# Enclosure_100x68_BHCP.net
KiCad netlist of a schematic drawn in EAGLE
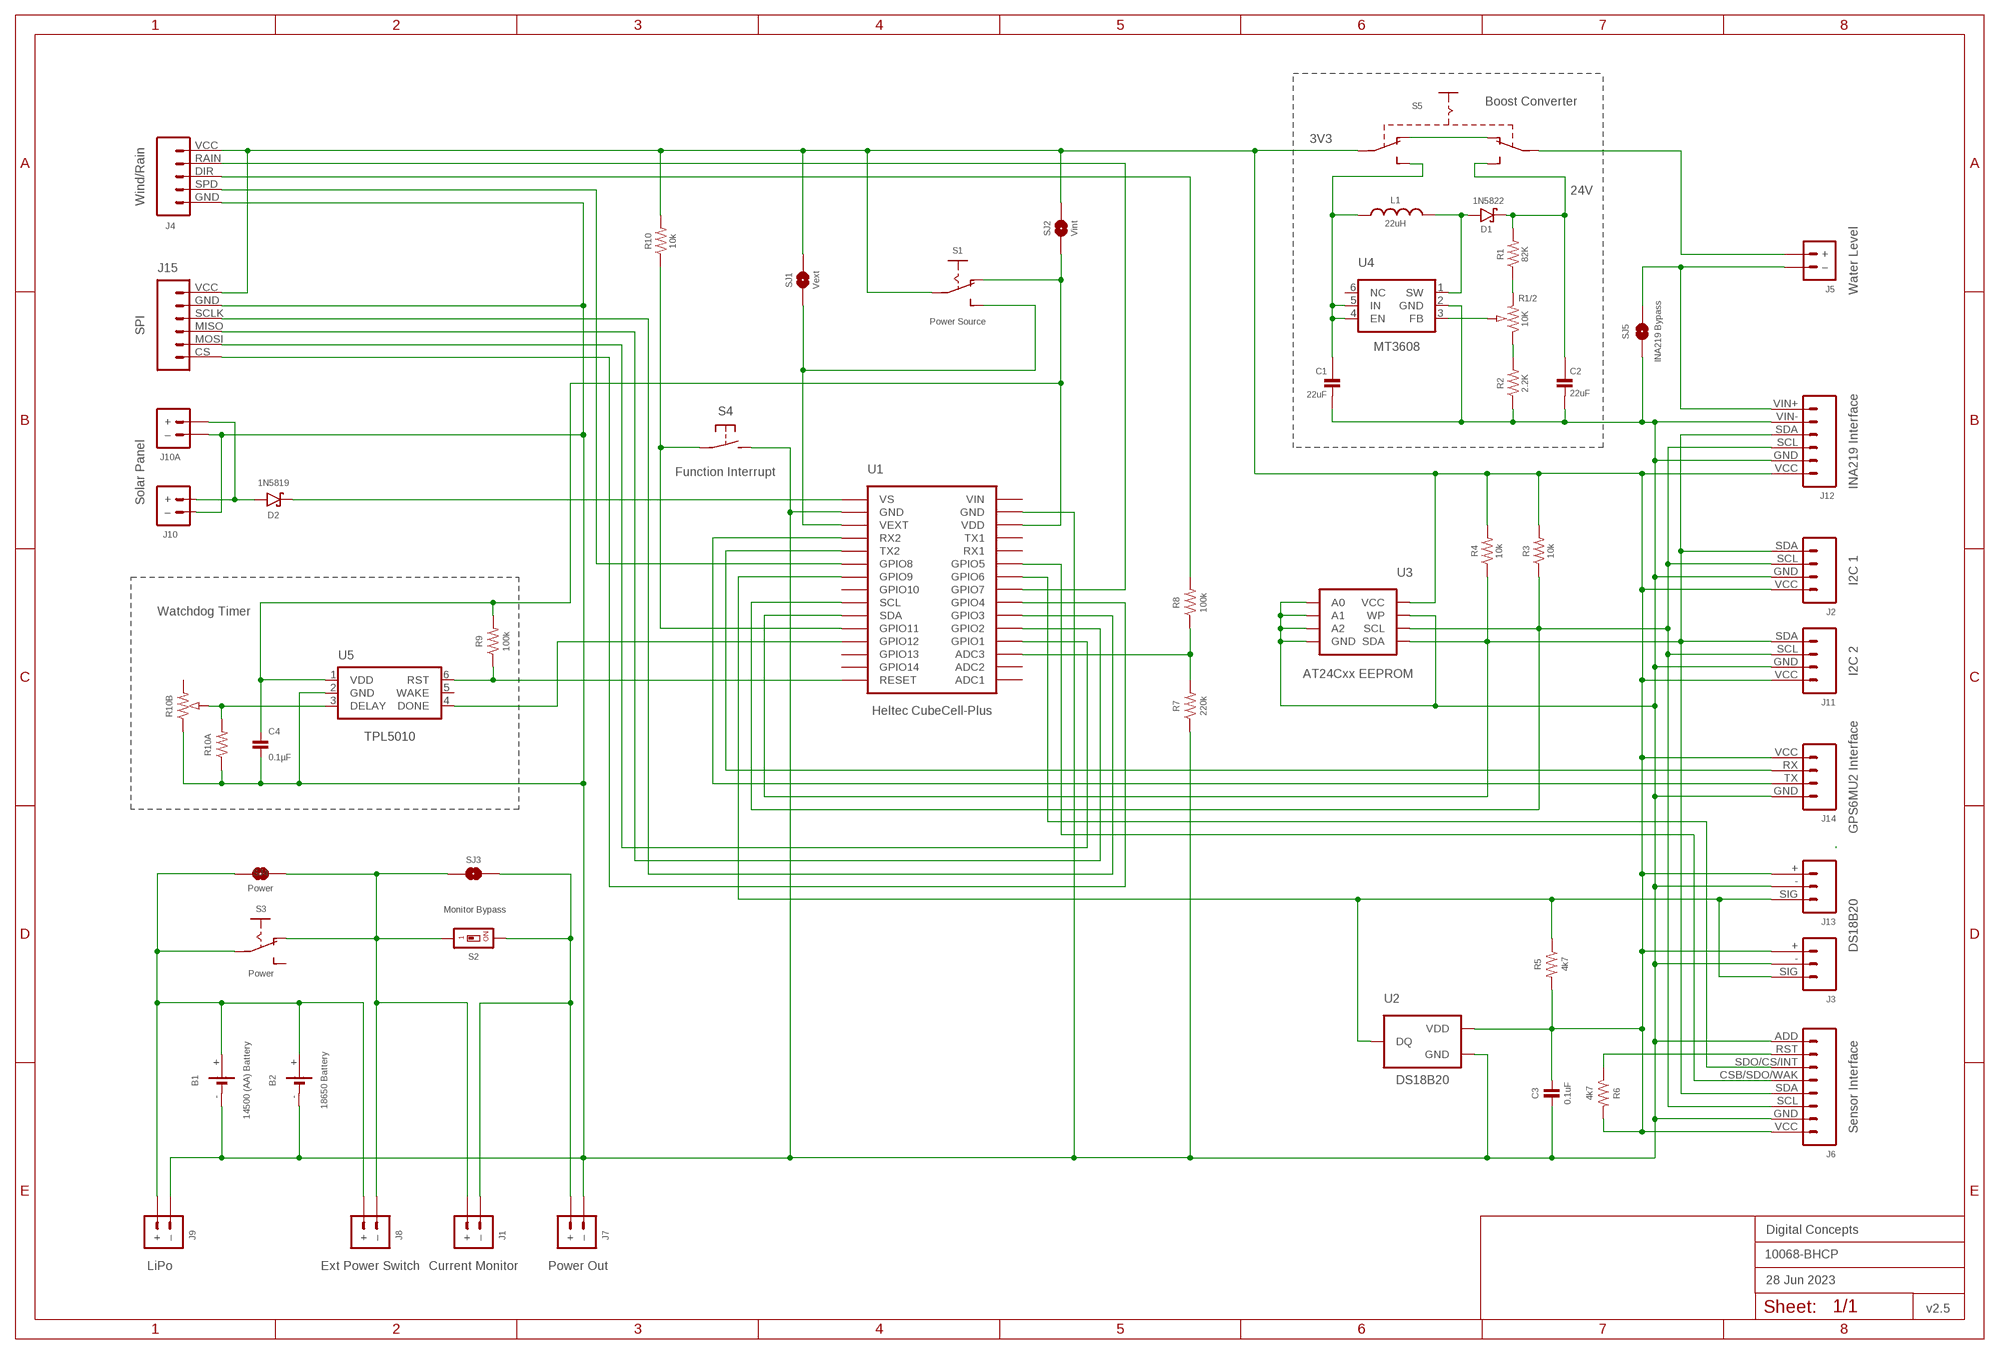
[diagram p0: schematic, sheet 1]

(export (version "E")
  (design (tool "Eeschema 10.0.6"))
  (components
    (comp (ref "B1")
      (value "14500 (AA) Battery")
      (footprint "eagle-import:BATTERY-14500")
      (libsource (lib "eagle-import") (part "BATTERY-HOLDER-14500(AA)"))
    )
    (comp (ref "B2")
      (value "18650 Battery")
      (footprint "eagle-import:BATTERY-18650")
      (libsource (lib "eagle-import") (part "BATTERY-HOLDER-18650"))
    )
    (comp (ref "C1")
      (value "22uF")
      (footprint "eagle-import:C1206")
      (libsource (lib "eagle-import") (part "CAPACITOR-1206"))
    )
    (comp (ref "C2")
      (value "22uF")
      (footprint "eagle-import:C1206")
      (libsource (lib "eagle-import") (part "CAPACITOR-1206"))
    )
    (comp (ref "C3")
      (value "0.1uF")
      (footprint "eagle-import:C0805")
      (libsource (lib "eagle-import") (part "CAPACITOR-0805"))
    )
    (comp (ref "C4")
      (value "0.1µF")
      (footprint "eagle-import:C0805")
      (libsource (lib "eagle-import") (part "CAPACITOR-0805"))
    )
    (comp (ref "D1")
      (value "1N5822")
      (footprint "eagle-import:DIODE_SMB")
      (libsource (lib "eagle-import") (part "DIODE-SCHOTTKY-1N5822"))
    )
    (comp (ref "D2")
      (value "1N5819")
      (footprint "eagle-import:SOD-123")
      (libsource (lib "eagle-import") (part "1N5819-SOD-123"))
    )
    (comp (ref "J1")
      (value "Current Monitor")
      (footprint "eagle-import:JST-PH2.0-2-HORIZONTAL")
      (libsource (lib "eagle-import") (part "JST-PH2.0-2-HORIZONTALJST-PTH-2"))
    )
    (comp (ref "J2")
      (value "I2C 1")
      (footprint "eagle-import:JST-PH2.0-4-VERTICAL-I2C")
      (libsource (lib "eagle-import") (part "JST-PH2.0-4-VERTICAL-I2C"))
    )
    (comp (ref "J3")
      (value "DS18B20")
      (footprint "eagle-import:JST-PH2.0-3-VERTICAL-SIG")
      (libsource (lib "eagle-import") (part "JST-PH2.0-3-VERTICAL-DS18B20"))
    )
    (comp (ref "J4")
      (value "Wind/Rain")
      (footprint "eagle-import:JST-PH2.0-5-DUAL-WEATHER")
      (libsource (lib "eagle-import") (part "JST-PH2.0-5-DUAL-WEATHER"))
    )
    (comp (ref "J5")
      (value "Water Level")
      (footprint "eagle-import:JST-PH2.0-2-DUAL-POWER")
      (libsource (lib "eagle-import") (part "JST-PH2.0-2-DUAL-POWERJST-PTH-2"))
    )
    (comp (ref "J6")
      (value "Sensor Interface")
      (footprint "eagle-import:CONN_08-SENSOR")
      (libsource (lib "eagle-import") (part "HEADER-1X8-SENSOR"))
    )
    (comp (ref "J7")
      (value "Power Out")
      (footprint "eagle-import:JST-GH1.25-2-HORIZONTAL")
      (libsource (lib "eagle-import") (part "JST-GH1.25-2-HORIZONTAL-POWER"))
    )
    (comp (ref "J8")
      (value "Ext Power Switch")
      (footprint "eagle-import:JST-PH2.0-2-DUAL-POWER")
      (libsource (lib "eagle-import") (part "JST-PH2.0-2-DUAL-POWERJST-PTH-2"))
    )
    (comp (ref "J9")
      (value "LiPo")
      (footprint "eagle-import:JST-PH2.0-2-HORIZONTAL-POWER")
      (libsource (lib "eagle-import") (part "JST-PH2.0-2-HORIZONTAL-POWERJST-PTH-2"))
    )
    (comp (ref "J10")
      (value "Solar Panel")
      (footprint "eagle-import:JST-PH2.0-2-VERTICAL=POWER")
      (libsource (lib "eagle-import") (part "JST-PH2.0-2-VERTICAL"))
    )
    (comp (ref "J10A")
      (value "JST-PH2.0-2-HORIZONTAL-POWERJST-PTH-2")
      (footprint "eagle-import:JST-PH2.0-2-HORIZONTAL-POWER")
      (libsource (lib "eagle-import") (part "JST-PH2.0-2-HORIZONTAL-POWERJST-PTH-2"))
    )
    (comp (ref "J11")
      (value "I2C 2")
      (footprint "eagle-import:JST-PH2.0-4-HORIZONTAL")
      (libsource (lib "eagle-import") (part "JST-PH2.0-I2C-MALE-HORIZONTAL"))
    )
    (comp (ref "J12")
      (value "INA219 Interface")
      (footprint "eagle-import:CONN_06-INA219")
      (libsource (lib "eagle-import") (part "INA219-I2C-MODULE"))
    )
    (comp (ref "J13")
      (value "JST-PH2.0-3-HORIZONTAL-DS18B20")
      (footprint "eagle-import:JST-PH2.0-DS18B20-HORIZONTAL")
      (libsource (lib "eagle-import") (part "JST-PH2.0-3-HORIZONTAL-DS18B20"))
    )
    (comp (ref "J14")
      (value "GPS6MU2 Interface")
      (footprint "eagle-import:CONN_04-GPS")
      (libsource (lib "eagle-import") (part "HEADER-1X4-GPS"))
    )
    (comp (ref "J15")
      (value "SPI")
      (footprint "eagle-import:JST-PH2.0-6-HORIZONTAL-SPI")
      (libsource (lib "eagle-import") (part "JST-PH2.0-6-HORIZONTAL-SPI"))
    )
    (comp (ref "L1")
      (value "22uH")
      (footprint "eagle-import:CDRH104R+6D28")
      (libsource (lib "eagle-import") (part "INDUCTOR-CDRH104R/6D28L5038P"))
    )
    (comp (ref "R1")
      (value "82K")
      (footprint "eagle-import:R0805")
      (libsource (lib "eagle-import") (part "RESISTORR0805"))
    )
    (comp (ref "R1/2")
      (value "10K")
      (footprint "eagle-import:RTRIM64P")
      (libsource (lib "eagle-import") (part "RESISTOR-TRIMM-BAOTER-H-US"))
    )
    (comp (ref "R2")
      (value "2.2K")
      (footprint "eagle-import:R0805")
      (libsource (lib "eagle-import") (part "RESISTORR0805"))
    )
    (comp (ref "R3")
      (value "10k")
      (footprint "eagle-import:R0805")
      (libsource (lib "eagle-import") (part "RESISTORR0805"))
    )
    (comp (ref "R4")
      (value "10k")
      (footprint "eagle-import:R0805")
      (libsource (lib "eagle-import") (part "RESISTORR0805"))
    )
    (comp (ref "R5")
      (value "4k7")
      (footprint "eagle-import:R0805")
      (libsource (lib "eagle-import") (part "RESISTORR0805"))
    )
    (comp (ref "R6")
      (value "4k7")
      (footprint "eagle-import:R0805")
      (libsource (lib "eagle-import") (part "RESISTORR0805"))
    )
    (comp (ref "R7")
      (value "220k")
      (footprint "eagle-import:R0805")
      (libsource (lib "eagle-import") (part "RESISTORR0805"))
    )
    (comp (ref "R8")
      (value "100k")
      (footprint "eagle-import:R0805")
      (libsource (lib "eagle-import") (part "RESISTORR0805"))
    )
    (comp (ref "R9")
      (value "100k")
      (footprint "eagle-import:R0805")
      (libsource (lib "eagle-import") (part "RESISTORR0805"))
    )
    (comp (ref "R10")
      (value "10k")
      (footprint "eagle-import:R0805")
      (libsource (lib "eagle-import") (part "RESISTORR0805"))
    )
    (comp (ref "R10A")
      (value "RESISTORR0805")
      (footprint "eagle-import:R0805")
      (libsource (lib "eagle-import") (part "RESISTORR0805"))
    )
    (comp (ref "R10B")
      (value "RESISTOR-TRIMM-33-US")
      (footprint "eagle-import:RTRIM3_3")
      (libsource (lib "eagle-import") (part "RESISTOR-TRIMM-33-US"))
    )
    (comp (ref "S1")
      (value "Power Source")
      (footprint "eagle-import:SWITCH-SPDT-SMT")
      (libsource (lib "eagle-import") (part "SWITCH-SLIDE-SPDT-SMT"))
    )
    (comp (ref "S2")
      (value "Monitor Bypass")
      (footprint "eagle-import:SMD-001")
      (libsource (lib "eagle-import") (part "SWITCH-DIP-SWS001"))
    )
    (comp (ref "S3")
      (value "Power")
      (footprint "eagle-import:SWITCH-SPDT-PTH")
      (libsource (lib "eagle-import") (part "SWITCH-SLIDE-SPDT-PTH"))
    )
    (comp (ref "S4")
      (value "Function Interrupt")
      (footprint "eagle-import:SWITCH-2-PAD")
      (libsource (lib "eagle-import") (part "SWITCH-MOMENTARY-2-PIN"))
    )
    (comp (ref "S5")
      (value "SWITCH-SLIDE-DPDT-PTH-S")
      (footprint "eagle-import:SWITCH-DPDT-PTH")
      (libsource (lib "eagle-import") (part "SWITCH-SLIDE-DPDT-PTH-S"))
    )
    (comp (ref "SJ1")
      (value "Vext")
      (footprint "eagle-import:SJ")
      (libsource (lib "eagle-import") (part "SJ"))
    )
    (comp (ref "SJ2")
      (value "Vint")
      (footprint "eagle-import:SJ-VIA-12")
      (libsource (lib "eagle-import") (part "SJ-V-12"))
    )
    (comp (ref "SJ3")
      (value "Monitor")
      (footprint "eagle-import:SJ")
      (libsource (lib "eagle-import") (part "SJ"))
    )
    (comp (ref "SJ4")
      (value "Power")
      (footprint "eagle-import:SJ")
      (libsource (lib "eagle-import") (part "SJ"))
    )
    (comp (ref "SJ5")
      (value "INA219 Bypass")
      (footprint "eagle-import:SJ")
      (libsource (lib "eagle-import") (part "SJ"))
    )
    (comp (ref "U1")
      (value "Heltec CubeCell-Plus")
      (footprint "eagle-import:HELTEC-CUBECELL=PLUS-X")
      (libsource (lib "eagle-import") (part "HELTEC-CUBECELL-PLUS-X"))
    )
    (comp (ref "U2")
      (value "DS18B20")
      (footprint "eagle-import:TO-92")
      (fields (field (name "MF") "Maxim Integrated"))
      (libsource (lib "eagle-import") (part "THERMOMETER-DS18B20"))
    )
    (comp (ref "U3")
      (value "AT24Cxx EEPROM")
      (footprint "eagle-import:SOP-8")
      (libsource (lib "eagle-import") (part "AT24CXX-EEPROM"))
    )
    (comp (ref "U4")
      (value "MT3608")
      (footprint "eagle-import:SOT-23-6")
      (libsource (lib "eagle-import") (part "MT3608"))
    )
    (comp (ref "U5")
      (value "TPL5010")
      (footprint "eagle-import:SOT-23-6")
      (libsource (lib "eagle-import") (part "TPL5010DDCR"))
    )
  )
  (nets
    (net (code "1") (name "/VIN") (class "Default")
      (node (ref "U1") (pin "VIN") (pinfunction "VIN_VIN") (pintype "power_in"))
    )
    (net (code "2") (name "Net-(D2-PadA)") (class "Default")
      (node (ref "D2") (pin "A") (pinfunction "A_A") (pintype "passive"))
      (node (ref "J10") (pin "+") (pinfunction "+_+") (pintype "power_in"))
      (node (ref "J10A") (pin "+") (pinfunction "+_+") (pintype "power_in"))
    )
    (net (code "3") (name "Net-(D2-PadC)") (class "Default")
      (node (ref "D2") (pin "C") (pinfunction "C_C") (pintype "passive"))
      (node (ref "U1") (pin "VS") (pinfunction "VS_VS") (pintype "power_in"))
    )
    (net (code "4") (name "Net-(J1-+)") (class "Default")
      (node (ref "J1") (pin "1") (pinfunction "+_1") (pintype "power_in"))
      (node (ref "J8") (pin "-") (pinfunction "–_-") (pintype "power_in"))
      (node (ref "S2") (pin "1") (pinfunction "1_1") (pintype "passive"))
      (node (ref "S3") (pin "1") (pinfunction "O_1") (pintype "passive"))
      (node (ref "SJ3") (pin "2") (pinfunction "2_2") (pintype "passive"))
      (node (ref "SJ4") (pin "1") (pinfunction "1_1") (pintype "passive"))
    )
    (net (code "5") (name "Net-(J1-–)") (class "Default")
      (node (ref "J1") (pin "2") (pinfunction "–_2") (pintype "power_in"))
      (node (ref "J7") (pin "+") (pinfunction "+_+") (pintype "power_in"))
      (node (ref "S2") (pin "2") (pinfunction "2_2") (pintype "passive"))
      (node (ref "SJ3") (pin "1") (pinfunction "1_1") (pintype "passive"))
    )
    (net (code "6") (name "Net-(J4-2)") (class "Default")
      (node (ref "J4") (pin "RAIN") (pinfunction "2_RAIN") (pintype "passive"))
      (node (ref "U1") (pin "GPIO7") (pinfunction "GPIO7_GPIO7") (pintype "bidirectional"))
    )
    (net (code "7") (name "Net-(J4-3)") (class "Default")
      (node (ref "J4") (pin "DIR") (pinfunction "3_DIR") (pintype "passive"))
      (node (ref "R8") (pin "2") (pinfunction "2_2") (pintype "passive"))
    )
    (net (code "8") (name "Net-(J4-4)") (class "Default")
      (node (ref "J4") (pin "SPD") (pinfunction "4_SPD") (pintype "passive"))
      (node (ref "U1") (pin "GPIO8") (pinfunction "GPIO8_GPIO8") (pintype "bidirectional"))
    )
    (net (code "9") (name "Net-(J6-5)") (class "Default")
      (node (ref "J6") (pin "CSB/SDO/WAK") (pinfunction "5_CSB/SDO/WAK") (pintype "passive"))
      (node (ref "U1") (pin "GPIO5") (pinfunction "GPIO5_GPIO5") (pintype "bidirectional"))
    )
    (net (code "10") (name "Net-(J6-6)") (class "Default")
      (node (ref "J6") (pin "SDO/CS/INT") (pinfunction "6_SDO/CS/INT") (pintype "passive"))
      (node (ref "U1") (pin "GPIO6") (pinfunction "GPIO6_GPIO6") (pintype "bidirectional"))
    )
    (net (code "11") (name "Net-(J6-7)") (class "Default")
      (node (ref "J6") (pin "RST") (pinfunction "7_RST") (pintype "passive"))
      (node (ref "R6") (pin "1") (pinfunction "1_1") (pintype "passive"))
    )
    (net (code "12") (name "Net-(J10-–)") (class "Default")
      (node (ref "B1") (pin "-") (pinfunction "-_-") (pintype "power_in"))
      (node (ref "B2") (pin "-") (pinfunction "-_-") (pintype "power_in"))
      (node (ref "C1") (pin "2") (pinfunction "2_2") (pintype "passive"))
      (node (ref "C2") (pin "2") (pinfunction "2_2") (pintype "passive"))
      (node (ref "C3") (pin "2") (pinfunction "2_2") (pintype "passive"))
      (node (ref "C4") (pin "2") (pinfunction "2_2") (pintype "passive"))
      (node (ref "J10") (pin "-") (pinfunction "–_-") (pintype "power_in"))
      (node (ref "J10A") (pin "-") (pinfunction "–_-") (pintype "power_in"))
      (node (ref "J11") (pin "GND") (pinfunction "2_GND") (pintype "passive"))
      (node (ref "J12") (pin "GND") (pinfunction "2_GND") (pintype "passive"))
      (node (ref "J12") (pin "VIN-") (pinfunction "5_VIN-") (pintype "passive"))
      (node (ref "J13") (pin "-") (pinfunction "2_-") (pintype "passive"))
      (node (ref "J14") (pin "GND") (pinfunction "4_GND") (pintype "passive"))
      (node (ref "J15") (pin "GND") (pinfunction "5_GND") (pintype "passive"))
      (node (ref "J2") (pin "GND") (pinfunction "3_GND") (pintype "passive"))
      (node (ref "J3") (pin "-") (pinfunction "2_-") (pintype "passive"))
      (node (ref "J4") (pin "GND") (pinfunction "5_GND") (pintype "passive"))
      (node (ref "J6") (pin "ADD") (pinfunction "8_ADD") (pintype "passive"))
      (node (ref "J6") (pin "GND") (pinfunction "2_GND") (pintype "passive"))
      (node (ref "J7") (pin "-") (pinfunction "–_-") (pintype "power_in"))
      (node (ref "J9") (pin "-") (pinfunction "–_-") (pintype "power_in"))
      (node (ref "R10A") (pin "1") (pinfunction "1_1") (pintype "passive"))
      (node (ref "R10B") (pin "1") (pinfunction "A_1") (pintype "passive"))
      (node (ref "R2") (pin "1") (pinfunction "1_1") (pintype "passive"))
      (node (ref "R7") (pin "1") (pinfunction "1_1") (pintype "passive"))
      (node (ref "S4") (pin "P$2") (pinfunction "S_P$2") (pintype "passive"))
      (node (ref "SJ5") (pin "1") (pinfunction "1_1") (pintype "passive"))
      (node (ref "U1") (pin "GND@14") (pinfunction "GND_GND@14") (pintype "power_in"))
      (node (ref "U1") (pin "GND@17") (pinfunction "GND_GND@17") (pintype "power_in"))
      (node (ref "U2") (pin "1") (pinfunction "GND_1") (pintype "power_in"))
      (node (ref "U3") (pin "P$1") (pinfunction "A0_P$1") (pintype "bidirectional"))
      (node (ref "U3") (pin "P$2") (pinfunction "A1_P$2") (pintype "bidirectional"))
      (node (ref "U3") (pin "P$3") (pinfunction "A2_P$3") (pintype "bidirectional"))
      (node (ref "U3") (pin "P$4") (pinfunction "GND_P$4") (pintype "bidirectional"))
      (node (ref "U3") (pin "P$7") (pinfunction "WP_P$7") (pintype "bidirectional"))
      (node (ref "U4") (pin "2") (pinfunction "GND_2") (pintype "power_in"))
      (node (ref "U5") (pin "2") (pinfunction "GND_2") (pintype "power_in"))
    )
    (net (code "13") (name "Net-(J11-1)") (class "Default")
      (node (ref "C3") (pin "1") (pinfunction "1_1") (pintype "passive"))
      (node (ref "J11") (pin "VCC") (pinfunction "1_VCC") (pintype "passive"))
      (node (ref "J12") (pin "VCC") (pinfunction "1_VCC") (pintype "passive"))
      (node (ref "J13") (pin "+") (pinfunction "3_+") (pintype "passive"))
      (node (ref "J14") (pin "VCC") (pinfunction "1_VCC") (pintype "passive"))
      (node (ref "J15") (pin "VCC") (pinfunction "6_VCC") (pintype "passive"))
      (node (ref "J2") (pin "VCC") (pinfunction "4_VCC") (pintype "passive"))
      (node (ref "J3") (pin "+") (pinfunction "3_+") (pintype "passive"))
      (node (ref "J4") (pin "VCC") (pinfunction "1_VCC") (pintype "passive"))
      (node (ref "J6") (pin "VCC") (pinfunction "1_VCC") (pintype "passive"))
      (node (ref "R10") (pin "2") (pinfunction "2_2") (pintype "passive"))
      (node (ref "R3") (pin "2") (pinfunction "2_2") (pintype "passive"))
      (node (ref "R4") (pin "2") (pinfunction "2_2") (pintype "passive"))
      (node (ref "R5") (pin "2") (pinfunction "2_2") (pintype "passive"))
      (node (ref "R6") (pin "2") (pinfunction "2_2") (pintype "passive"))
      (node (ref "S1") (pin "2") (pinfunction "P_2") (pintype "passive"))
      (node (ref "S5") (pin "P$5") (pinfunction "P2_P$5") (pintype "passive"))
      (node (ref "SJ1") (pin "2") (pinfunction "2_2") (pintype "passive"))
      (node (ref "SJ2") (pin "2") (pinfunction "2_2") (pintype "passive"))
      (node (ref "SJ2") (pin "2@V") (pinfunction "2_2@V") (pintype "passive"))
      (node (ref "U2") (pin "3") (pinfunction "VDD_3") (pintype "power_in"))
      (node (ref "U3") (pin "P$8") (pinfunction "VCC_P$8") (pintype "bidirectional"))
    )
    (net (code "14") (name "Net-(J11-3)") (class "Default")
      (node (ref "J11") (pin "SCL") (pinfunction "3_SCL") (pintype "passive"))
      (node (ref "J12") (pin "SCL") (pinfunction "3_SCL") (pintype "passive"))
      (node (ref "J2") (pin "SCL") (pinfunction "2_SCL") (pintype "passive"))
      (node (ref "J6") (pin "SCL") (pinfunction "3_SCL") (pintype "passive"))
      (node (ref "R3") (pin "1") (pinfunction "1_1") (pintype "passive"))
      (node (ref "U1") (pin "SCL") (pinfunction "SCL_SCL") (pintype "bidirectional"))
      (node (ref "U3") (pin "P$6") (pinfunction "SCL_P$6") (pintype "bidirectional"))
    )
    (net (code "15") (name "Net-(J11-4)") (class "Default")
      (node (ref "J11") (pin "SDA") (pinfunction "4_SDA") (pintype "passive"))
      (node (ref "J12") (pin "SDA") (pinfunction "4_SDA") (pintype "passive"))
      (node (ref "J2") (pin "SDA") (pinfunction "1_SDA") (pintype "passive"))
      (node (ref "J6") (pin "SDA") (pinfunction "4_SDA") (pintype "passive"))
      (node (ref "R4") (pin "1") (pinfunction "1_1") (pintype "passive"))
      (node (ref "U1") (pin "SDA") (pinfunction "SDA_SDA") (pintype "bidirectional"))
      (node (ref "U3") (pin "P$5") (pinfunction "SDA_P$5") (pintype "bidirectional"))
    )
    (net (code "16") (name "Net-(J12-6)") (class "Default")
      (node (ref "J12") (pin "VIN+") (pinfunction "6_VIN+") (pintype "passive"))
      (node (ref "J5") (pin "-") (pinfunction "–_-") (pintype "power_in"))
      (node (ref "SJ5") (pin "2") (pinfunction "2_2") (pintype "passive"))
    )
    (net (code "17") (name "Net-(J13-1)") (class "Default")
      (node (ref "J13") (pin "SIG") (pinfunction "1_SIG") (pintype "passive"))
      (node (ref "J3") (pin "SIG") (pinfunction "1_SIG") (pintype "passive"))
      (node (ref "R5") (pin "1") (pinfunction "1_1") (pintype "passive"))
      (node (ref "U1") (pin "GPIO9") (pinfunction "GPIO9_GPIO9") (pintype "bidirectional"))
      (node (ref "U2") (pin "2") (pinfunction "DQ_2") (pintype "bidirectional"))
    )
    (net (code "18") (name "Net-(J14-2)") (class "Default")
      (node (ref "J14") (pin "RX") (pinfunction "2_RX") (pintype "passive"))
      (node (ref "U1") (pin "TX2") (pinfunction "TX2_TX2") (pintype "bidirectional"))
    )
    (net (code "19") (name "Net-(J14-3)") (class "Default")
      (node (ref "J14") (pin "TX") (pinfunction "3_TX") (pintype "passive"))
      (node (ref "U1") (pin "RX2") (pinfunction "RX2_RX2") (pintype "bidirectional"))
    )
    (net (code "20") (name "Net-(J15-1)") (class "Default")
      (node (ref "J15") (pin "CS") (pinfunction "1_CS") (pintype "passive"))
      (node (ref "U1") (pin "GPIO4") (pinfunction "GPIO4_GPIO4") (pintype "bidirectional"))
    )
    (net (code "21") (name "Net-(J15-2)") (class "Default")
      (node (ref "J15") (pin "MOSI") (pinfunction "2_MOSI") (pintype "passive"))
      (node (ref "U1") (pin "GPIO1") (pinfunction "GPIO1_GPIO1") (pintype "bidirectional"))
    )
    (net (code "22") (name "Net-(J15-3)") (class "Default")
      (node (ref "J15") (pin "MISO") (pinfunction "3_MISO") (pintype "passive"))
      (node (ref "U1") (pin "GPIO2") (pinfunction "GPIO2_GPIO2") (pintype "bidirectional"))
    )
    (net (code "23") (name "Net-(J15-4)") (class "Default")
      (node (ref "J15") (pin "SCLK") (pinfunction "4_SCLK") (pintype "passive"))
      (node (ref "U1") (pin "GPIO3") (pinfunction "GPIO3_GPIO3") (pintype "bidirectional"))
    )
    (net (code "24") (name "Net-(R1/2-A)") (class "Default")
      (node (ref "R1/2") (pin "1") (pinfunction "A_1") (pintype "passive"))
      (node (ref "R2") (pin "2") (pinfunction "2_2") (pintype "passive"))
    )
    (net (code "25") (name "Net-(R1/2-E)") (class "Default")
      (node (ref "R1") (pin "1") (pinfunction "1_1") (pintype "passive"))
      (node (ref "R1/2") (pin "3") (pinfunction "E_3") (pintype "passive"))
    )
    (net (code "26") (name "Net-(R1/2-S)") (class "Default")
      (node (ref "R1/2") (pin "2") (pinfunction "S_2") (pintype "passive"))
      (node (ref "U4") (pin "3") (pinfunction "FB_3") (pintype "input"))
    )
    (net (code "27") (name "Net-(R7-Pad2)") (class "Default")
      (node (ref "R7") (pin "2") (pinfunction "2_2") (pintype "passive"))
      (node (ref "R8") (pin "1") (pinfunction "1_1") (pintype "passive"))
      (node (ref "U1") (pin "ADC3") (pinfunction "ADC3_ADC3") (pintype "bidirectional"))
    )
    (net (code "28") (name "Net-(R10B-S)") (class "Default")
      (node (ref "R10A") (pin "2") (pinfunction "2_2") (pintype "passive"))
      (node (ref "R10B") (pin "2") (pinfunction "S_2") (pintype "passive"))
      (node (ref "U5") (pin "3") (pinfunction "DELAY_3") (pintype "input"))
    )
    (net (code "29") (name "Net-(S1-O)") (class "Default")
      (node (ref "C4") (pin "1") (pinfunction "1_1") (pintype "passive"))
      (node (ref "R9") (pin "2") (pinfunction "2_2") (pintype "passive"))
      (node (ref "S1") (pin "1") (pinfunction "O_1") (pintype "passive"))
      (node (ref "SJ2") (pin "1") (pinfunction "1_1") (pintype "passive"))
      (node (ref "SJ2") (pin "1@V") (pinfunction "1_1@V") (pintype "passive"))
      (node (ref "U1") (pin "VDD") (pinfunction "VDD_VDD") (pintype "power_in"))
      (node (ref "U5") (pin "1") (pinfunction "VDD_1") (pintype "power_in"))
    )
    (net (code "30") (name "Net-(S1-S)") (class "Default")
      (node (ref "S1") (pin "3") (pinfunction "S_3") (pintype "passive"))
      (node (ref "SJ1") (pin "1") (pinfunction "1_1") (pintype "passive"))
      (node (ref "U1") (pin "VEXT") (pinfunction "VEXT_VEXT") (pintype "power_in"))
    )
    (net (code "31") (name "Net-(S3-P)") (class "Default")
      (node (ref "B1") (pin "+") (pinfunction "+_+") (pintype "power_in"))
      (node (ref "B2") (pin "+") (pinfunction "+_+") (pintype "power_in"))
      (node (ref "J8") (pin "+") (pinfunction "+_+") (pintype "power_in"))
      (node (ref "J9") (pin "+") (pinfunction "+_+") (pintype "power_in"))
      (node (ref "S3") (pin "2") (pinfunction "P_2") (pintype "passive"))
      (node (ref "SJ4") (pin "2") (pinfunction "2_2") (pintype "passive"))
    )
    (net (code "32") (name "Net-(S4-P)") (class "Default")
      (node (ref "R10") (pin "1") (pinfunction "1_1") (pintype "passive"))
      (node (ref "S4") (pin "P$1") (pinfunction "P_P$1") (pintype "passive"))
      (node (ref "U1") (pin "GPIO11") (pinfunction "GPIO11_GPIO11") (pintype "bidirectional"))
    )
    (net (code "33") (name "Net-(S5-O1)") (class "Default")
      (node (ref "S5") (pin "P$1") (pinfunction "O1_P$1") (pintype "passive"))
      (node (ref "S5") (pin "P$4") (pinfunction "O2_P$4") (pintype "passive"))
    )
    (net (code "34") (name "Net-(S5-P1)") (class "Default")
      (node (ref "J5") (pin "+") (pinfunction "+_+") (pintype "power_in"))
      (node (ref "S5") (pin "P$2") (pinfunction "P1_P$2") (pintype "passive"))
    )
    (net (code "35") (name "Net-(S5-S1)") (class "Default")
      (node (ref "C2") (pin "1") (pinfunction "1_1") (pintype "passive"))
      (node (ref "D1") (pin "C") (pinfunction "C_C") (pintype "passive"))
      (node (ref "R1") (pin "2") (pinfunction "2_2") (pintype "passive"))
      (node (ref "S5") (pin "P$3") (pinfunction "S1_P$3") (pintype "passive"))
    )
    (net (code "36") (name "Net-(S5-S2)") (class "Default")
      (node (ref "C1") (pin "1") (pinfunction "1_1") (pintype "passive"))
      (node (ref "L1") (pin "2") (pinfunction "2_2") (pintype "passive"))
      (node (ref "S5") (pin "P$6") (pinfunction "S2_P$6") (pintype "passive"))
      (node (ref "U4") (pin "4") (pinfunction "EN_4") (pintype "input"))
      (node (ref "U4") (pin "5") (pinfunction "IN_5") (pintype "power_in"))
    )
    (net (code "37") (name "Net-(U1-RESET)") (class "Default")
      (node (ref "R9") (pin "1") (pinfunction "1_1") (pintype "passive"))
      (node (ref "U1") (pin "RST") (pinfunction "RESET_RST") (pintype "bidirectional"))
      (node (ref "U5") (pin "6") (pinfunction "RST_6") (pintype "output"))
    )
    (net (code "38") (name "Net-(U4-SW)") (class "Default")
      (node (ref "D1") (pin "A") (pinfunction "A_A") (pintype "passive"))
      (node (ref "L1") (pin "1") (pinfunction "1_1") (pintype "passive"))
      (node (ref "U4") (pin "1") (pinfunction "SW_1") (pintype "power_in"))
    )
    (net (code "39") (name "Net-(U5-DONE)") (class "Default")
      (node (ref "U1") (pin "GPIO12") (pinfunction "GPIO12_GPIO12") (pintype "bidirectional"))
      (node (ref "U5") (pin "4") (pinfunction "DONE_4") (pintype "input"))
    )
    (net (code "40") (name "unconnected-(R10B-E-Pad3)") (class "Default")
      (node (ref "R10B") (pin "3") (pinfunction "E_3") (pintype "passive"))
    )
    (net (code "41") (name "unconnected-(S3-S-Pad3)") (class "Default")
      (node (ref "S3") (pin "3") (pinfunction "S_3") (pintype "passive"))
    )
    (net (code "42") (name "unconnected-(U1-PadADC1)") (class "Default")
      (node (ref "U1") (pin "ADC1") (pinfunction "ADC1_ADC1") (pintype "bidirectional"))
    )
    (net (code "43") (name "unconnected-(U1-PadADC2)") (class "Default")
      (node (ref "U1") (pin "ADC2") (pinfunction "ADC2_ADC2") (pintype "bidirectional"))
    )
    (net (code "44") (name "unconnected-(U1-PadGPIO10)") (class "Default")
      (node (ref "U1") (pin "GPIO10") (pinfunction "GPIO10_GPIO10") (pintype "bidirectional"))
    )
    (net (code "45") (name "unconnected-(U1-PadGPIO13)") (class "Default")
      (node (ref "U1") (pin "GPIO13") (pinfunction "GPIO13_GPIO13") (pintype "bidirectional"))
    )
    (net (code "46") (name "unconnected-(U1-PadGPIO14)") (class "Default")
      (node (ref "U1") (pin "GPIO14") (pinfunction "GPIO14_GPIO14") (pintype "bidirectional"))
    )
    (net (code "47") (name "unconnected-(U1-PadRX1)") (class "Default")
      (node (ref "U1") (pin "RX1") (pinfunction "RX1_RX1") (pintype "bidirectional"))
    )
    (net (code "48") (name "unconnected-(U1-PadTX1)") (class "Default")
      (node (ref "U1") (pin "TX1") (pinfunction "TX1_TX1") (pintype "bidirectional"))
    )
    (net (code "49") (name "unconnected-(U4-NC-Pad6)") (class "Default")
      (node (ref "U4") (pin "6") (pinfunction "NC_6") (pintype "no_connect"))
    )
    (net (code "50") (name "unconnected-(U5-WAKE-Pad5)") (class "Default")
      (node (ref "U5") (pin "5") (pinfunction "WAKE_5") (pintype "output"))
    )
  )
)
